# CATS-FAT-Accel.net
KiCad netlist of a schematic drawn in Altium Designer
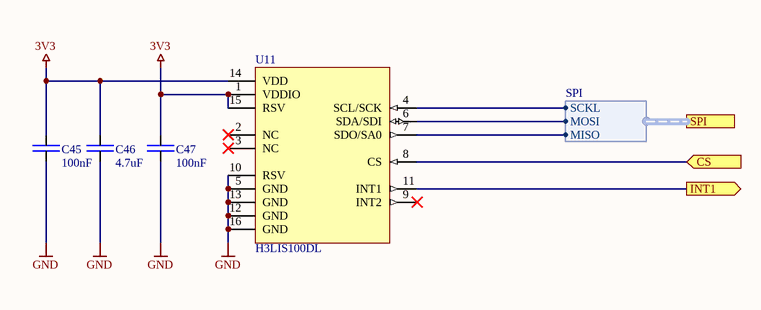
[diagram p0: CATS-FAT-Accel.SchDoc]

(export (version "E")
  (design (tool "Eeschema 10.0.6"))
  (components
    (comp (ref "C45")
      (value "100nF")
      (footprint "SMD Keramikkondensator 0603")
      (description "SMD Ceramic Capacitor E6")
      (libsource (lib "Ceramic Capacitors-E6") (part "E6 - 100nF"))
    )
    (comp (ref "C46")
      (value "4.7uF")
      (footprint "SMD Keramikkondensator 0603")
      (description "SMD Ceramic Capacitor E6")
      (libsource (lib "Ceramic Capacitors-E6") (part "E6 - 4.7uF"))
    )
    (comp (ref "C47")
      (value "100nF")
      (footprint "SMD Keramikkondensator 0603")
      (description "SMD Ceramic Capacitor E6")
      (libsource (lib "Ceramic Capacitors-E6") (part "E6 - 100nF"))
    )
    (comp (ref "U11")
      (value "H3LIS100DL")
      (footprint "SMD IC LGA-16 5/3")
      (description "Low-Power 100-g 3-Axis Digital Accelerometer")
      (libsource (lib "Sensors") (part "H3LIS100DL"))
    )
  )
  (nets
    (net (code "2") (name "/CS") (class "Default")
      (node (ref "U11") (pin "8") (pinfunction "CS_8") (pintype "input"))
    )
    (net (code "3") (name "/INT1") (class "Default")
      (node (ref "U11") (pin "11") (pinfunction "INT1_11") (pintype "output"))
    )
    (net (code "4") (name "/MISO") (class "Default")
      (node (ref "U11") (pin "7") (pinfunction "SDO/SA0_7") (pintype "output"))
    )
    (net (code "5") (name "/MOSI") (class "Default")
      (node (ref "U11") (pin "6") (pinfunction "SDA/SDI_6") (pintype "bidirectional"))
    )
    (net (code "6") (name "/SCKL") (class "Default")
      (node (ref "U11") (pin "4") (pinfunction "SCL/SCK_4") (pintype "input"))
    )
    (net (code "8") (name "3V3") (class "Default")
      (node (ref "C45") (pin "2") (pinfunction "2_2") (pintype "passive"))
      (node (ref "C46") (pin "2") (pinfunction "2_2") (pintype "passive"))
      (node (ref "C47") (pin "2") (pinfunction "2_2") (pintype "passive"))
      (node (ref "U11") (pin "1") (pinfunction "VDDIO_1") (pintype "passive"))
      (node (ref "U11") (pin "14") (pinfunction "VDD_14") (pintype "passive"))
      (node (ref "U11") (pin "15") (pinfunction "RSV_15") (pintype "passive"))
    )
    (net (code "9") (name "GND") (class "Default")
      (node (ref "C45") (pin "1") (pinfunction "1_1") (pintype "passive"))
      (node (ref "C46") (pin "1") (pinfunction "1_1") (pintype "passive"))
      (node (ref "C47") (pin "1") (pinfunction "1_1") (pintype "passive"))
      (node (ref "U11") (pin "10") (pinfunction "RSV_10") (pintype "passive"))
      (node (ref "U11") (pin "12") (pinfunction "GND_12") (pintype "passive"))
      (node (ref "U11") (pin "13") (pinfunction "GND_13") (pintype "passive"))
      (node (ref "U11") (pin "16") (pinfunction "GND_16") (pintype "passive"))
      (node (ref "U11") (pin "5") (pinfunction "GND_5") (pintype "passive"))
    )
    (net (code "10") (name "unconnected-(U11-INT2-Pad9)") (class "Default")
      (node (ref "U11") (pin "9") (pinfunction "INT2_9") (pintype "output+no_connect"))
    )
    (net (code "11") (name "unconnected-(U11-NC-Pad2)") (class "Default")
      (node (ref "U11") (pin "2") (pinfunction "NC_2") (pintype "passive+no_connect"))
    )
    (net (code "12") (name "unconnected-(U11-NC-Pad3)") (class "Default")
      (node (ref "U11") (pin "3") (pinfunction "NC_3") (pintype "passive+no_connect"))
    )
  )
)
